# SPI-I2C-Shield.net
KiCad netlist of a schematic drawn in Altium Designer
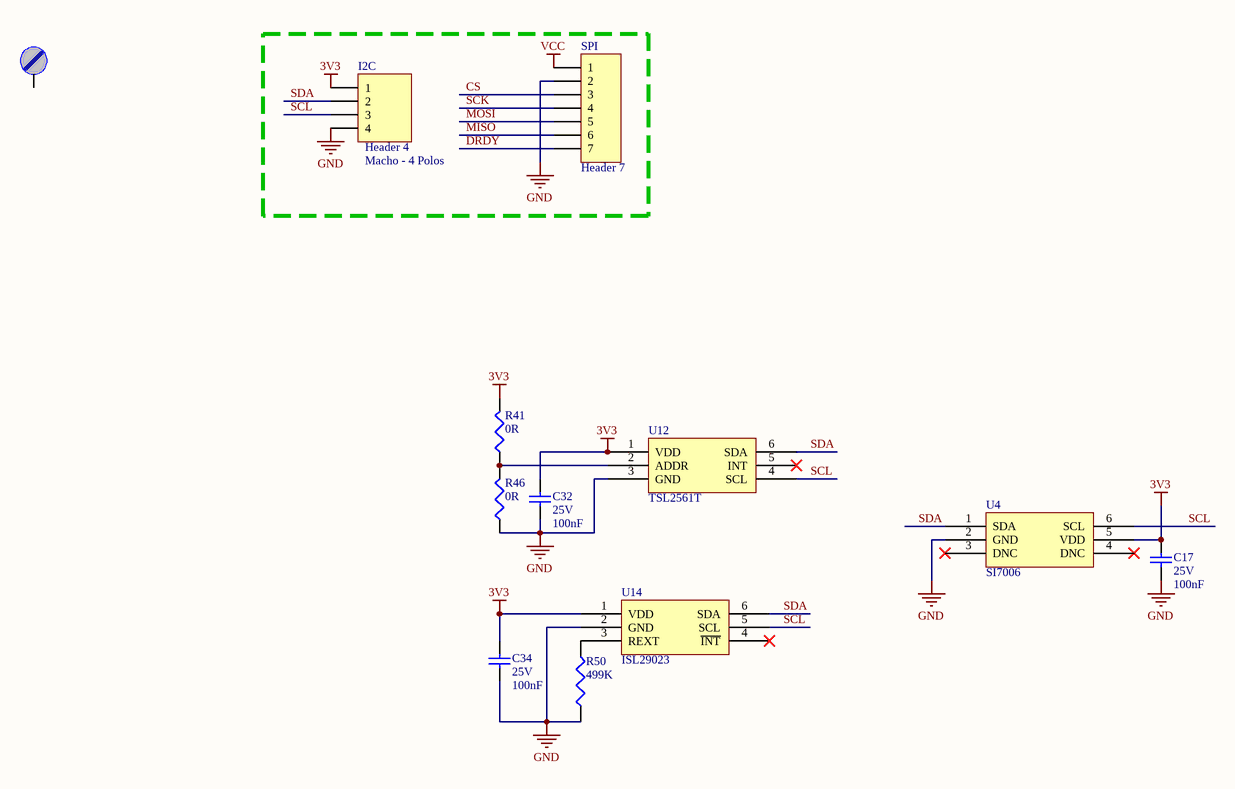
[diagram p0: SPI-I2C-Shield.SchDoc]

(export (version "E")
  (design (tool "Eeschema 10.0.6"))
  (components
    (comp (ref "C17")
      (value "100nF")
      (footprint "CC0603")
      (description "Capacitor (Semiconductor SIM Model)")
      (fields (field (name "TENSÃO") "25V") (field (name "Comment") "Capacitor Cerâmico"))
      (libsource (lib "NavarroCAP") (part "Cap 100nF 25V 0603 X7R"))
    )
    (comp (ref "C32")
      (value "100nF")
      (footprint "CC0603")
      (description "Capacitor (Semiconductor SIM Model)")
      (fields (field (name "TENSÃO") "25V") (field (name "Comment") "Capacitor Cerâmico"))
      (libsource (lib "NavarroCAP") (part "Cap 100nF 25V 0603 X7R"))
    )
    (comp (ref "C34")
      (value "100nF")
      (footprint "CC0603")
      (description "Capacitor (Semiconductor SIM Model)")
      (fields (field (name "TENSÃO") "25V") (field (name "Comment") "Capacitor Cerâmico"))
      (libsource (lib "NavarroCAP") (part "Cap 100nF 25V 0603 X7R"))
    )
    (comp (ref "I2C")
      (value "Header 4")
      (footprint "CONN HDR1X4")
      (description "Header, 4-Pin")
      (fields (field (name "ALTIUM_VALUE") "Macho - 4 Polos"))
      (libsource (lib "NavarroCON") (part "Header 4"))
    )
    (comp (ref "M2")
      (value "Furo de Fixação")
      (footprint "Furo_M3")
      (description "Furo para parafuso")
      (libsource (lib "Tecnoclade") (part "Parafuso"))
    )
    (comp (ref "R41")
      (value "0R")
      (footprint "CC0603")
      (description "Resistor")
      (libsource (lib "NavarroRES") (part "Res 0R 0603 1/10W"))
    )
    (comp (ref "R46")
      (value "0R")
      (footprint "CC0603")
      (description "Resistor")
      (libsource (lib "NavarroRES") (part "Res 0R 0603 1/10W"))
    )
    (comp (ref "R50")
      (value "499K")
      (footprint "CC0603")
      (description "Resistor")
      (libsource (lib "NavarroRES") (part "Res 499K 1% 0603 1/10W"))
    )
    (comp (ref "SPI")
      (value "Header 7")
      (footprint "CONN HDR1X7")
      (description "Header, 7-Pin")
      (libsource (lib "NavarroCON") (part "Header 7"))
    )
    (comp (ref "U4")
      (value "SI7006")
      (footprint "QFN3x3-6P")
      (description "SI7021-A20-GM1")
      (libsource (lib "Navarro") (part "SI7006"))
    )
    (comp (ref "U12")
      (value "TSL2561T")
      (footprint "TSL2561-TMB6")
      (description "Lux Meter")
      (libsource (lib "Navarro") (part "TSL2561T"))
    )
    (comp (ref "U14")
      (value "ISL29023")
      (footprint "QFN2x2-6")
      (description "Lux Meter")
      (libsource (lib "Navarro") (part "ISL29023"))
    )
  )
  (nets
    (net (code "1") (name "/CS") (class "Default")
      (node (ref "SPI") (pin "3") (pinfunction "3_3") (pintype "passive"))
    )
    (net (code "2") (name "/DRDY") (class "Default")
      (node (ref "SPI") (pin "7") (pinfunction "7_7") (pintype "passive"))
    )
    (net (code "3") (name "/MISO") (class "Default")
      (node (ref "SPI") (pin "6") (pinfunction "6_6") (pintype "passive"))
    )
    (net (code "4") (name "/MOSI") (class "Default")
      (node (ref "SPI") (pin "5") (pinfunction "5_5") (pintype "passive"))
    )
    (net (code "5") (name "/SCK") (class "Default")
      (node (ref "SPI") (pin "4") (pinfunction "4_4") (pintype "passive"))
    )
    (net (code "6") (name "/SCL") (class "Default")
      (node (ref "I2C") (pin "3") (pinfunction "3_3") (pintype "passive"))
      (node (ref "U12") (pin "4") (pinfunction "SCL_4") (pintype "passive"))
      (node (ref "U14") (pin "5") (pinfunction "SCL_5") (pintype "power_in"))
      (node (ref "U4") (pin "6") (pinfunction "SCL_6") (pintype "passive"))
    )
    (net (code "7") (name "/SDA") (class "Default")
      (node (ref "I2C") (pin "2") (pinfunction "2_2") (pintype "passive"))
      (node (ref "U12") (pin "6") (pinfunction "SDA_6") (pintype "passive"))
      (node (ref "U14") (pin "6") (pinfunction "SDA_6") (pintype "passive"))
      (node (ref "U4") (pin "1") (pinfunction "SDA_1") (pintype "passive"))
    )
    (net (code "8") (name "3V3") (class "Default")
      (node (ref "C17") (pin "2") (pinfunction "2_2") (pintype "passive"))
      (node (ref "C32") (pin "2") (pinfunction "2_2") (pintype "passive"))
      (node (ref "C34") (pin "2") (pinfunction "2_2") (pintype "passive"))
      (node (ref "I2C") (pin "1") (pinfunction "1_1") (pintype "passive"))
      (node (ref "R41") (pin "2") (pinfunction "2_2") (pintype "passive"))
      (node (ref "U12") (pin "1") (pinfunction "VDD_1") (pintype "passive"))
      (node (ref "U14") (pin "1") (pinfunction "VDD_1") (pintype "passive"))
      (node (ref "U4") (pin "5") (pinfunction "VDD_5") (pintype "power_in"))
    )
    (net (code "9") (name "GND") (class "Default")
      (node (ref "C17") (pin "1") (pinfunction "1_1") (pintype "passive"))
      (node (ref "C32") (pin "1") (pinfunction "1_1") (pintype "passive"))
      (node (ref "C34") (pin "1") (pinfunction "1_1") (pintype "passive"))
      (node (ref "I2C") (pin "4") (pinfunction "4_4") (pintype "passive"))
      (node (ref "R46") (pin "1") (pinfunction "1_1") (pintype "passive"))
      (node (ref "R50") (pin "1") (pinfunction "1_1") (pintype "passive"))
      (node (ref "SPI") (pin "2") (pinfunction "2_2") (pintype "passive"))
      (node (ref "U12") (pin "3") (pinfunction "GND_3") (pintype "passive"))
      (node (ref "U14") (pin "2") (pinfunction "GND_2") (pintype "passive"))
      (node (ref "U4") (pin "2") (pinfunction "GND_2") (pintype "passive"))
    )
    (net (code "10") (name "Net-(U12-ADDR)") (class "Default")
      (node (ref "R41") (pin "1") (pinfunction "1_1") (pintype "passive"))
      (node (ref "R46") (pin "2") (pinfunction "2_2") (pintype "passive"))
      (node (ref "U12") (pin "2") (pinfunction "ADDR_2") (pintype "passive"))
    )
    (net (code "11") (name "Net-(U14-REXT)") (class "Default")
      (node (ref "R50") (pin "2") (pinfunction "2_2") (pintype "passive"))
      (node (ref "U14") (pin "3") (pinfunction "REXT_3") (pintype "passive"))
    )
    (net (code "12") (name "VCC") (class "Default")
      (node (ref "SPI") (pin "1") (pinfunction "1_1") (pintype "passive"))
    )
    (net (code "13") (name "unconnected-(M2-PadX)") (class "Default")
      (node (ref "M2") (pin "X") (pinfunction "X_X") (pintype "passive"))
    )
    (net (code "14") (name "unconnected-(U4-DNC-Pad3)") (class "Default")
      (node (ref "U4") (pin "3") (pinfunction "DNC_3") (pintype "passive+no_connect"))
    )
    (net (code "15") (name "unconnected-(U4-DNC-Pad4)") (class "Default")
      (node (ref "U4") (pin "4") (pinfunction "DNC_4") (pintype "passive+no_connect"))
    )
    (net (code "16") (name "unconnected-(U12-INT-Pad5)") (class "Default")
      (node (ref "U12") (pin "5") (pinfunction "INT_5") (pintype "power_in+no_connect"))
    )
    (net (code "17") (name "unconnected-(U14-~{INT}-Pad4)") (class "Default")
      (node (ref "U14") (pin "4") (pinfunction "~{INT}_4") (pintype "passive+no_connect"))
    )
  )
)
